# AD7799.net
KiCad netlist of a schematic drawn in Altium Designer
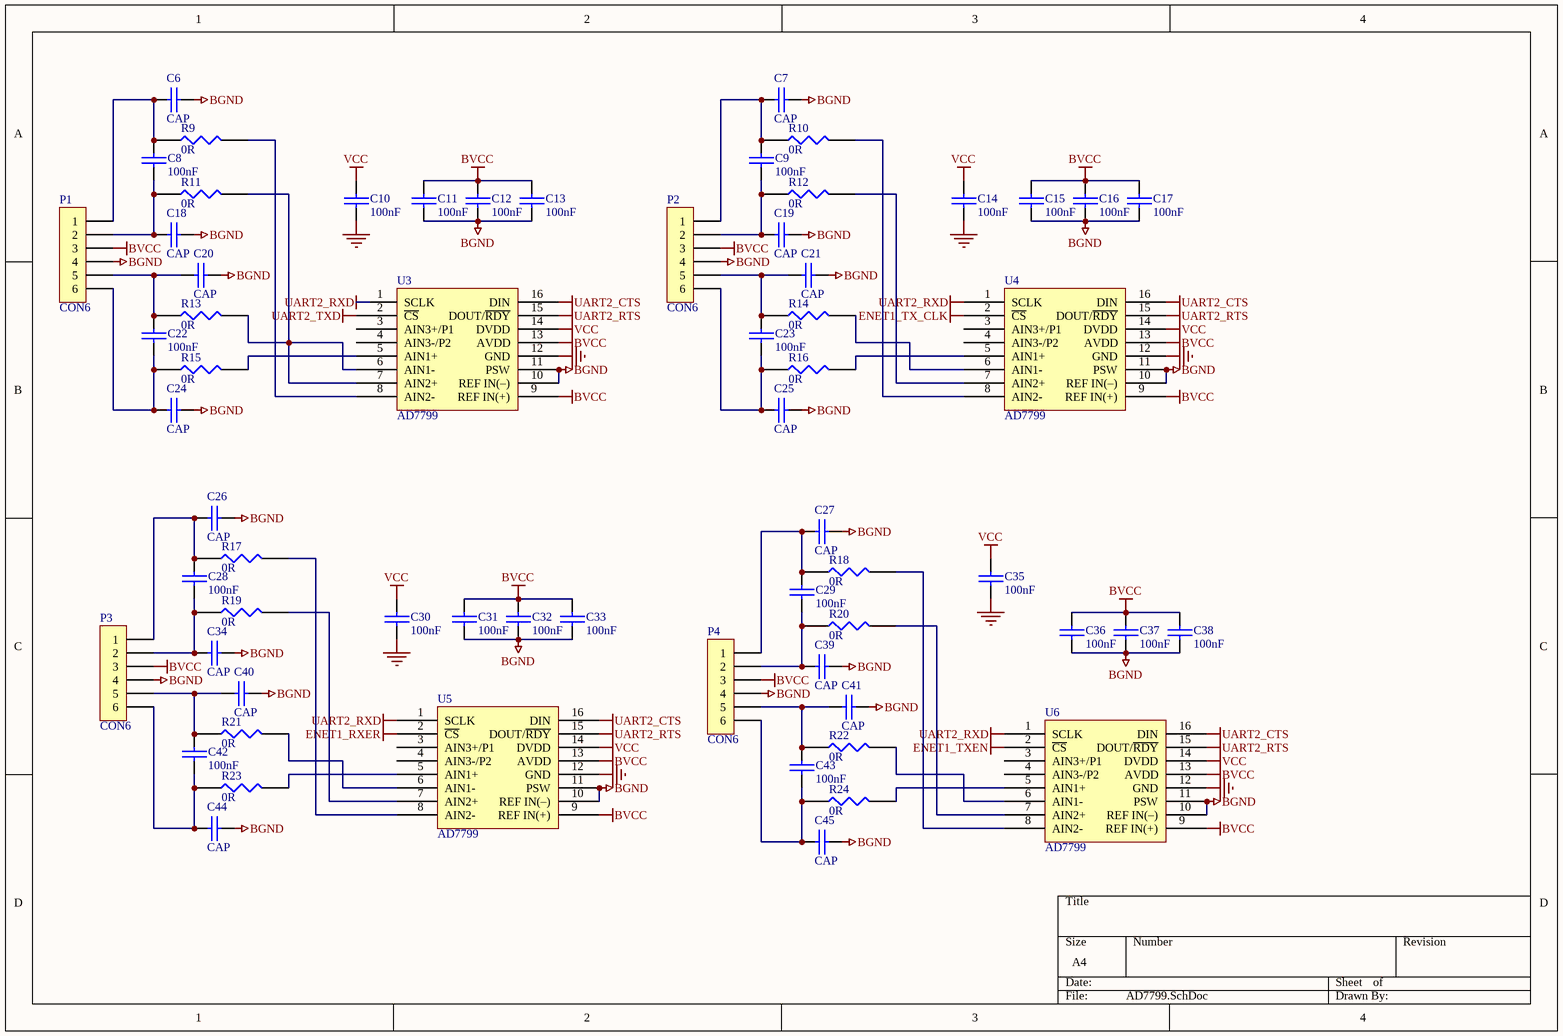
[diagram p0: AD7799.SchDoc]

(export (version "E")
  (design (tool "Eeschema 10.0.6"))
  (components
    (comp (ref "C6")
      (value "CAP")
      (footprint "0603_C")
      (description "Capacitor")
      (libsource (lib "*") (part "CAP"))
    )
    (comp (ref "C7")
      (value "CAP")
      (footprint "0603_C")
      (description "Capacitor")
      (libsource (lib "*") (part "CAP"))
    )
    (comp (ref "C8")
      (value "100nF")
      (footprint "0603_C")
      (description "Capacitor")
      (libsource (lib "*") (part "CAP"))
    )
    (comp (ref "C9")
      (value "100nF")
      (footprint "0603_C")
      (description "Capacitor")
      (libsource (lib "*") (part "CAP"))
    )
    (comp (ref "C10")
      (value "100nF")
      (footprint "0603_C")
      (description "Capacitor")
      (libsource (lib "*") (part "CAP"))
    )
    (comp (ref "C11")
      (value "100nF")
      (footprint "0603_C")
      (description "Capacitor")
      (libsource (lib "*") (part "CAP"))
    )
    (comp (ref "C12")
      (value "100nF")
      (footprint "0603_C")
      (description "Capacitor")
      (libsource (lib "*") (part "CAP"))
    )
    (comp (ref "C13")
      (value "100nF")
      (footprint "0603_C")
      (description "Capacitor")
      (libsource (lib "*") (part "CAP"))
    )
    (comp (ref "C14")
      (value "100nF")
      (footprint "0603_C")
      (description "Capacitor")
      (libsource (lib "*") (part "CAP"))
    )
    (comp (ref "C15")
      (value "100nF")
      (footprint "0603_C")
      (description "Capacitor")
      (libsource (lib "*") (part "CAP"))
    )
    (comp (ref "C16")
      (value "100nF")
      (footprint "0603_C")
      (description "Capacitor")
      (libsource (lib "*") (part "CAP"))
    )
    (comp (ref "C17")
      (value "100nF")
      (footprint "0603_C")
      (description "Capacitor")
      (libsource (lib "*") (part "CAP"))
    )
    (comp (ref "C18")
      (value "CAP")
      (footprint "0603_C")
      (description "Capacitor")
      (libsource (lib "*") (part "CAP"))
    )
    (comp (ref "C19")
      (value "CAP")
      (footprint "0603_C")
      (description "Capacitor")
      (libsource (lib "*") (part "CAP"))
    )
    (comp (ref "C20")
      (value "CAP")
      (footprint "0603_C")
      (description "Capacitor")
      (libsource (lib "*") (part "CAP"))
    )
    (comp (ref "C21")
      (value "CAP")
      (footprint "0603_C")
      (description "Capacitor")
      (libsource (lib "*") (part "CAP"))
    )
    (comp (ref "C22")
      (value "100nF")
      (footprint "0603_C")
      (description "Capacitor")
      (libsource (lib "*") (part "CAP"))
    )
    (comp (ref "C23")
      (value "100nF")
      (footprint "0603_C")
      (description "Capacitor")
      (libsource (lib "*") (part "CAP"))
    )
    (comp (ref "C24")
      (value "CAP")
      (footprint "0603_C")
      (description "Capacitor")
      (libsource (lib "*") (part "CAP"))
    )
    (comp (ref "C25")
      (value "CAP")
      (footprint "0603_C")
      (description "Capacitor")
      (libsource (lib "*") (part "CAP"))
    )
    (comp (ref "C26")
      (value "CAP")
      (footprint "0603_C")
      (description "Capacitor")
      (libsource (lib "*") (part "CAP"))
    )
    (comp (ref "C27")
      (value "CAP")
      (footprint "0603_C")
      (description "Capacitor")
      (libsource (lib "*") (part "CAP"))
    )
    (comp (ref "C28")
      (value "100nF")
      (footprint "0603_C")
      (description "Capacitor")
      (libsource (lib "*") (part "CAP"))
    )
    (comp (ref "C29")
      (value "100nF")
      (footprint "0603_C")
      (description "Capacitor")
      (libsource (lib "*") (part "CAP"))
    )
    (comp (ref "C30")
      (value "100nF")
      (footprint "0603_C")
      (description "Capacitor")
      (libsource (lib "*") (part "CAP"))
    )
    (comp (ref "C31")
      (value "100nF")
      (footprint "0603_C")
      (description "Capacitor")
      (libsource (lib "*") (part "CAP"))
    )
    (comp (ref "C32")
      (value "100nF")
      (footprint "0603_C")
      (description "Capacitor")
      (libsource (lib "*") (part "CAP"))
    )
    (comp (ref "C33")
      (value "100nF")
      (footprint "0603_C")
      (description "Capacitor")
      (libsource (lib "*") (part "CAP"))
    )
    (comp (ref "C34")
      (value "CAP")
      (footprint "0603_C")
      (description "Capacitor")
      (libsource (lib "*") (part "CAP"))
    )
    (comp (ref "C35")
      (value "100nF")
      (footprint "0603_C")
      (description "Capacitor")
      (libsource (lib "*") (part "CAP"))
    )
    (comp (ref "C36")
      (value "100nF")
      (footprint "0603_C")
      (description "Capacitor")
      (libsource (lib "*") (part "CAP"))
    )
    (comp (ref "C37")
      (value "100nF")
      (footprint "0603_C")
      (description "Capacitor")
      (libsource (lib "*") (part "CAP"))
    )
    (comp (ref "C38")
      (value "100nF")
      (footprint "0603_C")
      (description "Capacitor")
      (libsource (lib "*") (part "CAP"))
    )
    (comp (ref "C39")
      (value "CAP")
      (footprint "0603_C")
      (description "Capacitor")
      (libsource (lib "*") (part "CAP"))
    )
    (comp (ref "C40")
      (value "CAP")
      (footprint "0603_C")
      (description "Capacitor")
      (libsource (lib "*") (part "CAP"))
    )
    (comp (ref "C41")
      (value "CAP")
      (footprint "0603_C")
      (description "Capacitor")
      (libsource (lib "*") (part "CAP"))
    )
    (comp (ref "C42")
      (value "100nF")
      (footprint "0603_C")
      (description "Capacitor")
      (libsource (lib "*") (part "CAP"))
    )
    (comp (ref "C43")
      (value "100nF")
      (footprint "0603_C")
      (description "Capacitor")
      (libsource (lib "*") (part "CAP"))
    )
    (comp (ref "C44")
      (value "CAP")
      (footprint "0603_C")
      (description "Capacitor")
      (libsource (lib "*") (part "CAP"))
    )
    (comp (ref "C45")
      (value "CAP")
      (footprint "0603_C")
      (description "Capacitor")
      (libsource (lib "*") (part "CAP"))
    )
    (comp (ref "P1")
      (value "CON6")
      (footprint "KF128-3.81-6P")
      (description "Connector")
      (libsource (lib "*") (part "CON6"))
    )
    (comp (ref "P2")
      (value "CON6")
      (footprint "KF128-3.81-6P")
      (description "Connector")
      (libsource (lib "*") (part "CON6"))
    )
    (comp (ref "P3")
      (value "CON6")
      (footprint "KF128-3.81-6P")
      (description "Connector")
      (libsource (lib "*") (part "CON6"))
    )
    (comp (ref "P4")
      (value "CON6")
      (footprint "KF128-3.81-6P")
      (description "Connector")
      (libsource (lib "*") (part "CON6"))
    )
    (comp (ref "R9") (value "0R") (footprint "0603_R") (libsource (lib "*") (part "RES1")))
    (comp (ref "R10") (value "0R") (footprint "0603_R") (libsource (lib "*") (part "RES1")))
    (comp (ref "R11") (value "0R") (footprint "0603_R") (libsource (lib "*") (part "RES1")))
    (comp (ref "R12") (value "0R") (footprint "0603_R") (libsource (lib "*") (part "RES1")))
    (comp (ref "R13") (value "0R") (footprint "0603_R") (libsource (lib "*") (part "RES1")))
    (comp (ref "R14") (value "0R") (footprint "0603_R") (libsource (lib "*") (part "RES1")))
    (comp (ref "R15") (value "0R") (footprint "0603_R") (libsource (lib "*") (part "RES1")))
    (comp (ref "R16") (value "0R") (footprint "0603_R") (libsource (lib "*") (part "RES1")))
    (comp (ref "R17") (value "0R") (footprint "0603_R") (libsource (lib "*") (part "RES1")))
    (comp (ref "R18") (value "0R") (footprint "0603_R") (libsource (lib "*") (part "RES1")))
    (comp (ref "R19") (value "0R") (footprint "0603_R") (libsource (lib "*") (part "RES1")))
    (comp (ref "R20") (value "0R") (footprint "0603_R") (libsource (lib "*") (part "RES1")))
    (comp (ref "R21") (value "0R") (footprint "0603_R") (libsource (lib "*") (part "RES1")))
    (comp (ref "R22") (value "0R") (footprint "0603_R") (libsource (lib "*") (part "RES1")))
    (comp (ref "R23") (value "0R") (footprint "0603_R") (libsource (lib "*") (part "RES1")))
    (comp (ref "R24") (value "0R") (footprint "0603_R") (libsource (lib "*") (part "RES1")))
    (comp (ref "U3") (value "AD7799") (footprint "TSSOP16") (libsource (lib "*") (part "AD7799")))
    (comp (ref "U4") (value "AD7799") (footprint "TSSOP16") (libsource (lib "*") (part "AD7799")))
    (comp (ref "U5") (value "AD7799") (footprint "TSSOP16") (libsource (lib "*") (part "AD7799")))
    (comp (ref "U6") (value "AD7799") (footprint "TSSOP16") (libsource (lib "*") (part "AD7799")))
  )
  (nets
    (net (code "1") (name "BGND") (class "Default")
      (node (ref "C11") (pin "2") (pinfunction "2_2") (pintype "passive"))
      (node (ref "C12") (pin "2") (pinfunction "2_2") (pintype "passive"))
      (node (ref "C13") (pin "2") (pinfunction "2_2") (pintype "passive"))
      (node (ref "C15") (pin "2") (pinfunction "2_2") (pintype "passive"))
      (node (ref "C16") (pin "2") (pinfunction "2_2") (pintype "passive"))
      (node (ref "C17") (pin "2") (pinfunction "2_2") (pintype "passive"))
      (node (ref "C18") (pin "2") (pinfunction "2_2") (pintype "passive"))
      (node (ref "C19") (pin "2") (pinfunction "2_2") (pintype "passive"))
      (node (ref "C20") (pin "2") (pinfunction "2_2") (pintype "passive"))
      (node (ref "C21") (pin "2") (pinfunction "2_2") (pintype "passive"))
      (node (ref "C24") (pin "2") (pinfunction "2_2") (pintype "passive"))
      (node (ref "C25") (pin "2") (pinfunction "2_2") (pintype "passive"))
      (node (ref "C26") (pin "2") (pinfunction "2_2") (pintype "passive"))
      (node (ref "C27") (pin "2") (pinfunction "2_2") (pintype "passive"))
      (node (ref "C31") (pin "2") (pinfunction "2_2") (pintype "passive"))
      (node (ref "C32") (pin "2") (pinfunction "2_2") (pintype "passive"))
      (node (ref "C33") (pin "2") (pinfunction "2_2") (pintype "passive"))
      (node (ref "C34") (pin "2") (pinfunction "2_2") (pintype "passive"))
      (node (ref "C36") (pin "2") (pinfunction "2_2") (pintype "passive"))
      (node (ref "C37") (pin "2") (pinfunction "2_2") (pintype "passive"))
      (node (ref "C38") (pin "2") (pinfunction "2_2") (pintype "passive"))
      (node (ref "C39") (pin "2") (pinfunction "2_2") (pintype "passive"))
      (node (ref "C40") (pin "2") (pinfunction "2_2") (pintype "passive"))
      (node (ref "C41") (pin "2") (pinfunction "2_2") (pintype "passive"))
      (node (ref "C44") (pin "2") (pinfunction "2_2") (pintype "passive"))
      (node (ref "C45") (pin "2") (pinfunction "2_2") (pintype "passive"))
      (node (ref "C6") (pin "2") (pinfunction "2_2") (pintype "passive"))
      (node (ref "C7") (pin "2") (pinfunction "2_2") (pintype "passive"))
      (node (ref "P1") (pin "4") (pinfunction "4_4") (pintype "passive"))
      (node (ref "P2") (pin "4") (pinfunction "4_4") (pintype "passive"))
      (node (ref "P3") (pin "4") (pinfunction "4_4") (pintype "passive"))
      (node (ref "P4") (pin "4") (pinfunction "4_4") (pintype "passive"))
      (node (ref "U3") (pin "10") (pinfunction "REF_IN(–)_10") (pintype "passive"))
      (node (ref "U3") (pin "11") (pinfunction "PSW_11") (pintype "passive"))
      (node (ref "U4") (pin "10") (pinfunction "REF_IN(–)_10") (pintype "passive"))
      (node (ref "U4") (pin "11") (pinfunction "PSW_11") (pintype "passive"))
      (node (ref "U5") (pin "10") (pinfunction "REF_IN(–)_10") (pintype "passive"))
      (node (ref "U5") (pin "11") (pinfunction "PSW_11") (pintype "passive"))
      (node (ref "U6") (pin "10") (pinfunction "REF_IN(–)_10") (pintype "passive"))
      (node (ref "U6") (pin "11") (pinfunction "PSW_11") (pintype "passive"))
    )
    (net (code "2") (name "BVCC") (class "Default")
      (node (ref "C11") (pin "1") (pinfunction "1_1") (pintype "passive"))
      (node (ref "C12") (pin "1") (pinfunction "1_1") (pintype "passive"))
      (node (ref "C13") (pin "1") (pinfunction "1_1") (pintype "passive"))
      (node (ref "C15") (pin "1") (pinfunction "1_1") (pintype "passive"))
      (node (ref "C16") (pin "1") (pinfunction "1_1") (pintype "passive"))
      (node (ref "C17") (pin "1") (pinfunction "1_1") (pintype "passive"))
      (node (ref "C31") (pin "1") (pinfunction "1_1") (pintype "passive"))
      (node (ref "C32") (pin "1") (pinfunction "1_1") (pintype "passive"))
      (node (ref "C33") (pin "1") (pinfunction "1_1") (pintype "passive"))
      (node (ref "C36") (pin "1") (pinfunction "1_1") (pintype "passive"))
      (node (ref "C37") (pin "1") (pinfunction "1_1") (pintype "passive"))
      (node (ref "C38") (pin "1") (pinfunction "1_1") (pintype "passive"))
      (node (ref "P1") (pin "3") (pinfunction "3_3") (pintype "passive"))
      (node (ref "P2") (pin "3") (pinfunction "3_3") (pintype "passive"))
      (node (ref "P3") (pin "3") (pinfunction "3_3") (pintype "passive"))
      (node (ref "P4") (pin "3") (pinfunction "3_3") (pintype "passive"))
      (node (ref "U3") (pin "13") (pinfunction "AVDD_13") (pintype "passive"))
      (node (ref "U3") (pin "9") (pinfunction "REF_IN(+)_9") (pintype "passive"))
      (node (ref "U4") (pin "13") (pinfunction "AVDD_13") (pintype "passive"))
      (node (ref "U4") (pin "9") (pinfunction "REF_IN(+)_9") (pintype "passive"))
      (node (ref "U5") (pin "13") (pinfunction "AVDD_13") (pintype "passive"))
      (node (ref "U5") (pin "9") (pinfunction "REF_IN(+)_9") (pintype "passive"))
      (node (ref "U6") (pin "13") (pinfunction "AVDD_13") (pintype "passive"))
      (node (ref "U6") (pin "9") (pinfunction "REF_IN(+)_9") (pintype "passive"))
    )
    (net (code "3") (name "ENET1_RXER") (class "Default")
      (node (ref "U5") (pin "2") (pinfunction "~{CS}_2") (pintype "passive"))
    )
    (net (code "4") (name "ENET1_TXEN") (class "Default")
      (node (ref "U6") (pin "2") (pinfunction "~{CS}_2") (pintype "passive"))
    )
    (net (code "5") (name "ENET1_TX_CLK") (class "Default")
      (node (ref "U4") (pin "2") (pinfunction "~{CS}_2") (pintype "passive"))
    )
    (net (code "6") (name "GND") (class "Default")
      (node (ref "C10") (pin "2") (pinfunction "2_2") (pintype "passive"))
      (node (ref "C14") (pin "2") (pinfunction "2_2") (pintype "passive"))
      (node (ref "C30") (pin "2") (pinfunction "2_2") (pintype "passive"))
      (node (ref "C35") (pin "2") (pinfunction "2_2") (pintype "passive"))
      (node (ref "U3") (pin "12") (pinfunction "GND_12") (pintype "passive"))
      (node (ref "U4") (pin "12") (pinfunction "GND_12") (pintype "passive"))
      (node (ref "U5") (pin "12") (pinfunction "GND_12") (pintype "passive"))
      (node (ref "U6") (pin "12") (pinfunction "GND_12") (pintype "passive"))
    )
    (net (code "7") (name "Net-(C6-Pad1)") (class "Default")
      (node (ref "C6") (pin "1") (pinfunction "1_1") (pintype "passive"))
      (node (ref "C8") (pin "1") (pinfunction "1_1") (pintype "passive"))
      (node (ref "P1") (pin "1") (pinfunction "1_1") (pintype "passive"))
      (node (ref "R9") (pin "1") (pinfunction "1_1") (pintype "passive"))
    )
    (net (code "8") (name "Net-(C7-Pad1)") (class "Default")
      (node (ref "C7") (pin "1") (pinfunction "1_1") (pintype "passive"))
      (node (ref "C9") (pin "1") (pinfunction "1_1") (pintype "passive"))
      (node (ref "P2") (pin "1") (pinfunction "1_1") (pintype "passive"))
      (node (ref "R10") (pin "1") (pinfunction "1_1") (pintype "passive"))
    )
    (net (code "9") (name "Net-(C18-Pad1)") (class "Default")
      (node (ref "C18") (pin "1") (pinfunction "1_1") (pintype "passive"))
      (node (ref "C8") (pin "2") (pinfunction "2_2") (pintype "passive"))
      (node (ref "P1") (pin "2") (pinfunction "2_2") (pintype "passive"))
      (node (ref "R11") (pin "1") (pinfunction "1_1") (pintype "passive"))
    )
    (net (code "10") (name "Net-(C19-Pad1)") (class "Default")
      (node (ref "C19") (pin "1") (pinfunction "1_1") (pintype "passive"))
      (node (ref "C9") (pin "2") (pinfunction "2_2") (pintype "passive"))
      (node (ref "P2") (pin "2") (pinfunction "2_2") (pintype "passive"))
      (node (ref "R12") (pin "1") (pinfunction "1_1") (pintype "passive"))
    )
    (net (code "11") (name "Net-(C20-Pad1)") (class "Default")
      (node (ref "C20") (pin "1") (pinfunction "1_1") (pintype "passive"))
      (node (ref "C22") (pin "1") (pinfunction "1_1") (pintype "passive"))
      (node (ref "P1") (pin "5") (pinfunction "5_5") (pintype "passive"))
      (node (ref "R13") (pin "1") (pinfunction "1_1") (pintype "passive"))
    )
    (net (code "12") (name "Net-(C21-Pad1)") (class "Default")
      (node (ref "C21") (pin "1") (pinfunction "1_1") (pintype "passive"))
      (node (ref "C23") (pin "1") (pinfunction "1_1") (pintype "passive"))
      (node (ref "P2") (pin "5") (pinfunction "5_5") (pintype "passive"))
      (node (ref "R14") (pin "1") (pinfunction "1_1") (pintype "passive"))
    )
    (net (code "13") (name "Net-(C22-Pad2)") (class "Default")
      (node (ref "C22") (pin "2") (pinfunction "2_2") (pintype "passive"))
      (node (ref "C24") (pin "1") (pinfunction "1_1") (pintype "passive"))
      (node (ref "P1") (pin "6") (pinfunction "6_6") (pintype "passive"))
      (node (ref "R15") (pin "1") (pinfunction "1_1") (pintype "passive"))
    )
    (net (code "14") (name "Net-(C23-Pad2)") (class "Default")
      (node (ref "C23") (pin "2") (pinfunction "2_2") (pintype "passive"))
      (node (ref "C25") (pin "1") (pinfunction "1_1") (pintype "passive"))
      (node (ref "P2") (pin "6") (pinfunction "6_6") (pintype "passive"))
      (node (ref "R16") (pin "1") (pinfunction "1_1") (pintype "passive"))
    )
    (net (code "15") (name "Net-(C26-Pad1)") (class "Default")
      (node (ref "C26") (pin "1") (pinfunction "1_1") (pintype "passive"))
      (node (ref "C28") (pin "1") (pinfunction "1_1") (pintype "passive"))
      (node (ref "P3") (pin "1") (pinfunction "1_1") (pintype "passive"))
      (node (ref "R17") (pin "1") (pinfunction "1_1") (pintype "passive"))
    )
    (net (code "16") (name "Net-(C27-Pad1)") (class "Default")
      (node (ref "C27") (pin "1") (pinfunction "1_1") (pintype "passive"))
      (node (ref "C29") (pin "1") (pinfunction "1_1") (pintype "passive"))
      (node (ref "P4") (pin "1") (pinfunction "1_1") (pintype "passive"))
      (node (ref "R18") (pin "1") (pinfunction "1_1") (pintype "passive"))
    )
    (net (code "17") (name "Net-(C28-Pad2)") (class "Default")
      (node (ref "C28") (pin "2") (pinfunction "2_2") (pintype "passive"))
      (node (ref "C34") (pin "1") (pinfunction "1_1") (pintype "passive"))
      (node (ref "P3") (pin "2") (pinfunction "2_2") (pintype "passive"))
      (node (ref "R19") (pin "1") (pinfunction "1_1") (pintype "passive"))
    )
    (net (code "18") (name "Net-(C29-Pad2)") (class "Default")
      (node (ref "C29") (pin "2") (pinfunction "2_2") (pintype "passive"))
      (node (ref "C39") (pin "1") (pinfunction "1_1") (pintype "passive"))
      (node (ref "P4") (pin "2") (pinfunction "2_2") (pintype "passive"))
      (node (ref "R20") (pin "1") (pinfunction "1_1") (pintype "passive"))
    )
    (net (code "19") (name "Net-(C40-Pad1)") (class "Default")
      (node (ref "C40") (pin "1") (pinfunction "1_1") (pintype "passive"))
      (node (ref "C42") (pin "1") (pinfunction "1_1") (pintype "passive"))
      (node (ref "P3") (pin "5") (pinfunction "5_5") (pintype "passive"))
      (node (ref "R21") (pin "1") (pinfunction "1_1") (pintype "passive"))
    )
    (net (code "20") (name "Net-(C41-Pad1)") (class "Default")
      (node (ref "C41") (pin "1") (pinfunction "1_1") (pintype "passive"))
      (node (ref "C43") (pin "1") (pinfunction "1_1") (pintype "passive"))
      (node (ref "P4") (pin "5") (pinfunction "5_5") (pintype "passive"))
      (node (ref "R22") (pin "1") (pinfunction "1_1") (pintype "passive"))
    )
    (net (code "21") (name "Net-(C42-Pad2)") (class "Default")
      (node (ref "C42") (pin "2") (pinfunction "2_2") (pintype "passive"))
      (node (ref "C44") (pin "1") (pinfunction "1_1") (pintype "passive"))
      (node (ref "P3") (pin "6") (pinfunction "6_6") (pintype "passive"))
      (node (ref "R23") (pin "1") (pinfunction "1_1") (pintype "passive"))
    )
    (net (code "22") (name "Net-(C43-Pad2)") (class "Default")
      (node (ref "C43") (pin "2") (pinfunction "2_2") (pintype "passive"))
      (node (ref "C45") (pin "1") (pinfunction "1_1") (pintype "passive"))
      (node (ref "P4") (pin "6") (pinfunction "6_6") (pintype "passive"))
      (node (ref "R24") (pin "1") (pinfunction "1_1") (pintype "passive"))
    )
    (net (code "23") (name "Net-(U3-AIN1+)") (class "Default")
      (node (ref "R15") (pin "2") (pinfunction "2_2") (pintype "passive"))
      (node (ref "U3") (pin "5") (pinfunction "AIN1+_5") (pintype "passive"))
    )
    (net (code "24") (name "Net-(U3-AIN1-)") (class "Default")
      (node (ref "R11") (pin "2") (pinfunction "2_2") (pintype "passive"))
      (node (ref "R13") (pin "2") (pinfunction "2_2") (pintype "passive"))
      (node (ref "U3") (pin "6") (pinfunction "AIN1-_6") (pintype "passive"))
      (node (ref "U3") (pin "7") (pinfunction "AIN2+_7") (pintype "passive"))
    )
    (net (code "25") (name "Net-(U3-AIN2-)") (class "Default")
      (node (ref "R9") (pin "2") (pinfunction "2_2") (pintype "passive"))
      (node (ref "U3") (pin "8") (pinfunction "AIN2-_8") (pintype "passive"))
    )
    (net (code "26") (name "Net-(U4-AIN1+)") (class "Default")
      (node (ref "R16") (pin "2") (pinfunction "2_2") (pintype "passive"))
      (node (ref "U4") (pin "5") (pinfunction "AIN1+_5") (pintype "passive"))
    )
    (net (code "27") (name "Net-(U4-AIN1-)") (class "Default")
      (node (ref "R14") (pin "2") (pinfunction "2_2") (pintype "passive"))
      (node (ref "U4") (pin "6") (pinfunction "AIN1-_6") (pintype "passive"))
    )
    (net (code "28") (name "Net-(U4-AIN2+)") (class "Default")
      (node (ref "R12") (pin "2") (pinfunction "2_2") (pintype "passive"))
      (node (ref "U4") (pin "7") (pinfunction "AIN2+_7") (pintype "passive"))
    )
    (net (code "29") (name "Net-(U4-AIN2-)") (class "Default")
      (node (ref "R10") (pin "2") (pinfunction "2_2") (pintype "passive"))
      (node (ref "U4") (pin "8") (pinfunction "AIN2-_8") (pintype "passive"))
    )
    (net (code "30") (name "Net-(U5-AIN1+)") (class "Default")
      (node (ref "R23") (pin "2") (pinfunction "2_2") (pintype "passive"))
      (node (ref "U5") (pin "5") (pinfunction "AIN1+_5") (pintype "passive"))
    )
    (net (code "31") (name "Net-(U5-AIN1-)") (class "Default")
      (node (ref "R21") (pin "2") (pinfunction "2_2") (pintype "passive"))
      (node (ref "U5") (pin "6") (pinfunction "AIN1-_6") (pintype "passive"))
    )
    (net (code "32") (name "Net-(U5-AIN2+)") (class "Default")
      (node (ref "R19") (pin "2") (pinfunction "2_2") (pintype "passive"))
      (node (ref "U5") (pin "7") (pinfunction "AIN2+_7") (pintype "passive"))
    )
    (net (code "33") (name "Net-(U5-AIN2-)") (class "Default")
      (node (ref "R17") (pin "2") (pinfunction "2_2") (pintype "passive"))
      (node (ref "U5") (pin "8") (pinfunction "AIN2-_8") (pintype "passive"))
    )
    (net (code "34") (name "Net-(U6-AIN1+)") (class "Default")
      (node (ref "R24") (pin "2") (pinfunction "2_2") (pintype "passive"))
      (node (ref "U6") (pin "5") (pinfunction "AIN1+_5") (pintype "passive"))
    )
    (net (code "35") (name "Net-(U6-AIN1-)") (class "Default")
      (node (ref "R22") (pin "2") (pinfunction "2_2") (pintype "passive"))
      (node (ref "U6") (pin "6") (pinfunction "AIN1-_6") (pintype "passive"))
    )
    (net (code "36") (name "Net-(U6-AIN2+)") (class "Default")
      (node (ref "R20") (pin "2") (pinfunction "2_2") (pintype "passive"))
      (node (ref "U6") (pin "7") (pinfunction "AIN2+_7") (pintype "passive"))
    )
    (net (code "37") (name "Net-(U6-AIN2-)") (class "Default")
      (node (ref "R18") (pin "2") (pinfunction "2_2") (pintype "passive"))
      (node (ref "U6") (pin "8") (pinfunction "AIN2-_8") (pintype "passive"))
    )
    (net (code "38") (name "UART2_CTS") (class "Default")
      (node (ref "U3") (pin "16") (pinfunction "DIN_16") (pintype "passive"))
      (node (ref "U4") (pin "16") (pinfunction "DIN_16") (pintype "passive"))
      (node (ref "U5") (pin "16") (pinfunction "DIN_16") (pintype "passive"))
      (node (ref "U6") (pin "16") (pinfunction "DIN_16") (pintype "passive"))
    )
    (net (code "39") (name "UART2_RTS") (class "Default")
      (node (ref "U3") (pin "15") (pinfunction "DOUT/~{RDY}_15") (pintype "passive"))
      (node (ref "U4") (pin "15") (pinfunction "DOUT/~{RDY}_15") (pintype "passive"))
      (node (ref "U5") (pin "15") (pinfunction "DOUT/~{RDY}_15") (pintype "passive"))
      (node (ref "U6") (pin "15") (pinfunction "DOUT/~{RDY}_15") (pintype "passive"))
    )
    (net (code "40") (name "UART2_RXD") (class "Default")
      (node (ref "U3") (pin "1") (pinfunction "SCLK_1") (pintype "passive"))
      (node (ref "U4") (pin "1") (pinfunction "SCLK_1") (pintype "passive"))
      (node (ref "U5") (pin "1") (pinfunction "SCLK_1") (pintype "passive"))
      (node (ref "U6") (pin "1") (pinfunction "SCLK_1") (pintype "passive"))
    )
    (net (code "41") (name "UART2_TXD") (class "Default")
      (node (ref "U3") (pin "2") (pinfunction "~{CS}_2") (pintype "passive"))
    )
    (net (code "42") (name "VCC") (class "Default")
      (node (ref "C10") (pin "1") (pinfunction "1_1") (pintype "passive"))
      (node (ref "C14") (pin "1") (pinfunction "1_1") (pintype "passive"))
      (node (ref "C30") (pin "1") (pinfunction "1_1") (pintype "passive"))
      (node (ref "C35") (pin "1") (pinfunction "1_1") (pintype "passive"))
      (node (ref "U3") (pin "14") (pinfunction "DVDD_14") (pintype "passive"))
      (node (ref "U4") (pin "14") (pinfunction "DVDD_14") (pintype "passive"))
      (node (ref "U5") (pin "14") (pinfunction "DVDD_14") (pintype "passive"))
      (node (ref "U6") (pin "14") (pinfunction "DVDD_14") (pintype "passive"))
    )
    (net (code "43") (name "unconnected-(U3-AIN3+{slash}P1-Pad3)") (class "Default")
      (node (ref "U3") (pin "3") (pinfunction "AIN3+/P1_3") (pintype "passive"))
    )
    (net (code "44") (name "unconnected-(U3-AIN3-{slash}P2-Pad4)") (class "Default")
      (node (ref "U3") (pin "4") (pinfunction "AIN3-/P2_4") (pintype "passive"))
    )
    (net (code "45") (name "unconnected-(U4-AIN3+{slash}P1-Pad3)") (class "Default")
      (node (ref "U4") (pin "3") (pinfunction "AIN3+/P1_3") (pintype "passive"))
    )
    (net (code "46") (name "unconnected-(U4-AIN3-{slash}P2-Pad4)") (class "Default")
      (node (ref "U4") (pin "4") (pinfunction "AIN3-/P2_4") (pintype "passive"))
    )
    (net (code "47") (name "unconnected-(U5-AIN3+{slash}P1-Pad3)") (class "Default")
      (node (ref "U5") (pin "3") (pinfunction "AIN3+/P1_3") (pintype "passive"))
    )
    (net (code "48") (name "unconnected-(U5-AIN3-{slash}P2-Pad4)") (class "Default")
      (node (ref "U5") (pin "4") (pinfunction "AIN3-/P2_4") (pintype "passive"))
    )
    (net (code "49") (name "unconnected-(U6-AIN3+{slash}P1-Pad3)") (class "Default")
      (node (ref "U6") (pin "3") (pinfunction "AIN3+/P1_3") (pintype "passive"))
    )
    (net (code "50") (name "unconnected-(U6-AIN3-{slash}P2-Pad4)") (class "Default")
      (node (ref "U6") (pin "4") (pinfunction "AIN3-/P2_4") (pintype "passive"))
    )
  )
)
